# L3D_Main_Board_v2.net
KiCad netlist of a schematic drawn in EAGLE
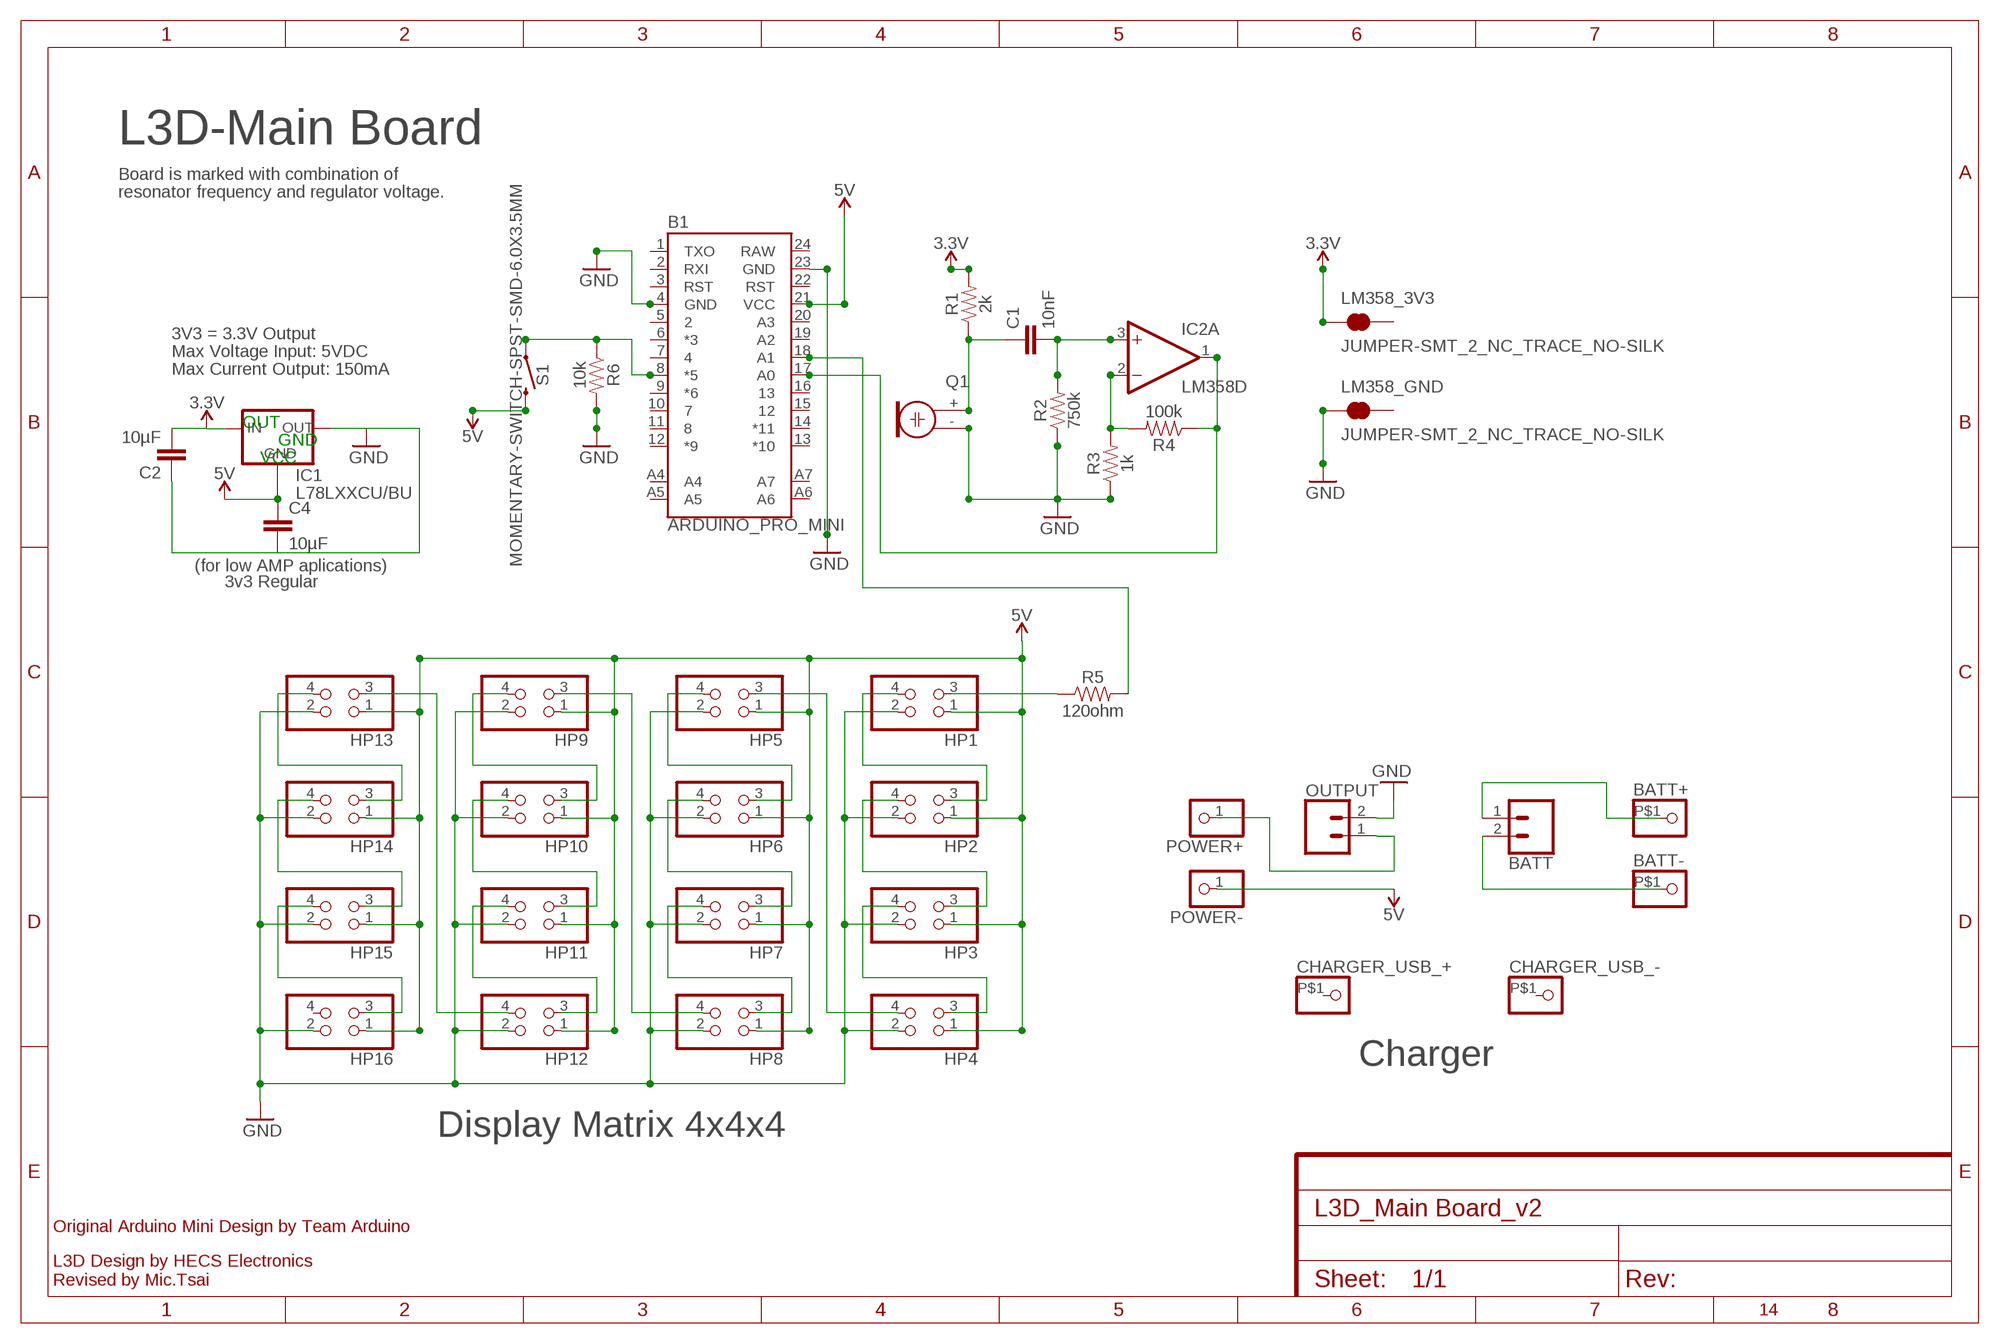
[diagram p0: schematic, sheet 1]

(export (version "E")
  (design (tool "Eeschema 10.0.6"))
  (components
    (comp (ref "B1")
      (value "ARDUINO_PRO_MINI")
      (footprint "eagle-import:ARDUINO_PRO_MINI")
      (libsource (lib "eagle-import") (part "ARDUINO_PRO_MINI"))
    )
    (comp (ref "BATT")
      (value "CONN_02")
      (footprint "eagle-import:1X02")
      (libsource (lib "eagle-import") (part "CONN_02"))
    )
    (comp (ref "BATT+")
      (value "PINHD-1X1-BIGPOGO")
      (footprint "eagle-import:1X1-BIGPOGO")
      (libsource (lib "eagle-import") (part "PINHD-1X1-BIGPOGO"))
    )
    (comp (ref "BATT-")
      (value "PINHD-1X1-BIGPOGO")
      (footprint "eagle-import:1X1-BIGPOGO")
      (libsource (lib "eagle-import") (part "PINHD-1X1-BIGPOGO"))
    )
    (comp (ref "C1")
      (value "10nF")
      (footprint "eagle-import:0805")
      (libsource (lib "eagle-import") (part "0.33UF/330NF-0805-50V-10%"))
    )
    (comp (ref "C2")
      (value "10µF")
      (footprint "eagle-import:0805")
      (libsource (lib "eagle-import") (part "0.33UF/330NF-0805-50V-10%"))
    )
    (comp (ref "C4")
      (value "10µF")
      (footprint "eagle-import:0805")
      (libsource (lib "eagle-import") (part "0.33UF/330NF-0805-50V-10%"))
    )
    (comp (ref "CHARGER_USB_+")
      (value "PINHD-1X1-BIGPOGO")
      (footprint "eagle-import:1X1-BIGPOGO")
      (libsource (lib "eagle-import") (part "PINHD-1X1-BIGPOGO"))
    )
    (comp (ref "CHARGER_USB_-")
      (value "PINHD-1X1-BIGPOGO")
      (footprint "eagle-import:1X1-BIGPOGO")
      (libsource (lib "eagle-import") (part "PINHD-1X1-BIGPOGO"))
    )
    (comp (ref "HP1")
      (value "PINHD-2X2_2.00")
      (footprint "eagle-import:2X02M")
      (libsource (lib "eagle-import") (part "PINHD-2X2_2.00"))
    )
    (comp (ref "HP2")
      (value "PINHD-2X2_2.00")
      (footprint "eagle-import:2X02M")
      (libsource (lib "eagle-import") (part "PINHD-2X2_2.00"))
    )
    (comp (ref "HP3")
      (value "PINHD-2X2_2.00")
      (footprint "eagle-import:2X02M")
      (libsource (lib "eagle-import") (part "PINHD-2X2_2.00"))
    )
    (comp (ref "HP4")
      (value "PINHD-2X2_2.00")
      (footprint "eagle-import:2X02M")
      (libsource (lib "eagle-import") (part "PINHD-2X2_2.00"))
    )
    (comp (ref "HP5")
      (value "PINHD-2X2_2.00")
      (footprint "eagle-import:2X02M")
      (libsource (lib "eagle-import") (part "PINHD-2X2_2.00"))
    )
    (comp (ref "HP6")
      (value "PINHD-2X2_2.00")
      (footprint "eagle-import:2X02M")
      (libsource (lib "eagle-import") (part "PINHD-2X2_2.00"))
    )
    (comp (ref "HP7")
      (value "PINHD-2X2_2.00")
      (footprint "eagle-import:2X02M")
      (libsource (lib "eagle-import") (part "PINHD-2X2_2.00"))
    )
    (comp (ref "HP8")
      (value "PINHD-2X2_2.00")
      (footprint "eagle-import:2X02M")
      (libsource (lib "eagle-import") (part "PINHD-2X2_2.00"))
    )
    (comp (ref "HP9")
      (value "PINHD-2X2_2.00")
      (footprint "eagle-import:2X02M")
      (libsource (lib "eagle-import") (part "PINHD-2X2_2.00"))
    )
    (comp (ref "HP10")
      (value "PINHD-2X2_2.00")
      (footprint "eagle-import:2X02M")
      (libsource (lib "eagle-import") (part "PINHD-2X2_2.00"))
    )
    (comp (ref "HP11")
      (value "PINHD-2X2_2.00")
      (footprint "eagle-import:2X02M")
      (libsource (lib "eagle-import") (part "PINHD-2X2_2.00"))
    )
    (comp (ref "HP12")
      (value "PINHD-2X2_2.00")
      (footprint "eagle-import:2X02M")
      (libsource (lib "eagle-import") (part "PINHD-2X2_2.00"))
    )
    (comp (ref "HP13")
      (value "PINHD-2X2_2.00")
      (footprint "eagle-import:2X02M")
      (libsource (lib "eagle-import") (part "PINHD-2X2_2.00"))
    )
    (comp (ref "HP14")
      (value "PINHD-2X2_2.00")
      (footprint "eagle-import:2X02M")
      (libsource (lib "eagle-import") (part "PINHD-2X2_2.00"))
    )
    (comp (ref "HP15")
      (value "PINHD-2X2_2.00")
      (footprint "eagle-import:2X02M")
      (libsource (lib "eagle-import") (part "PINHD-2X2_2.00"))
    )
    (comp (ref "HP16")
      (value "PINHD-2X2_2.00")
      (footprint "eagle-import:2X02M")
      (libsource (lib "eagle-import") (part "PINHD-2X2_2.00"))
    )
    (comp (ref "IC1")
      (value "L78LXXCU/BU")
      (footprint "eagle-import:SOT89")
      (libsource (lib "eagle-import") (part "L78LXXCU/BU"))
    )
    (comp (ref "IC2")
      (value "LM358D")
      (footprint "eagle-import:SO08")
      (libsource (lib "eagle-import") (part "LM358D"))
    )
    (comp (ref "LM358_3V3")
      (value "JUMPER-SMT_2_NC_TRACE_NO-SILK")
      (footprint "eagle-import:SMT-JUMPER_2_NC_TRACE_NO-SILK")
      (libsource (lib "eagle-import") (part "JUMPER-SMT_2_NC_TRACE_NO-SILK"))
    )
    (comp (ref "LM358_GND")
      (value "JUMPER-SMT_2_NC_TRACE_NO-SILK")
      (footprint "eagle-import:SMT-JUMPER_2_NC_TRACE_NO-SILK")
      (libsource (lib "eagle-import") (part "JUMPER-SMT_2_NC_TRACE_NO-SILK"))
    )
    (comp (ref "OUTPUT")
      (value "CONN_02")
      (footprint "eagle-import:1X02")
      (libsource (lib "eagle-import") (part "CONN_02"))
    )
    (comp (ref "POWER+")
      (value "PINHD-1X1")
      (footprint "eagle-import:1X01")
      (libsource (lib "eagle-import") (part "PINHD-1X1"))
    )
    (comp (ref "POWER-")
      (value "PINHD-1X1")
      (footprint "eagle-import:1X01")
      (libsource (lib "eagle-import") (part "PINHD-1X1"))
    )
    (comp (ref "Q1")
      (value "ELECTRET")
      (footprint "eagle-import:9.7ELECTRET")
      (libsource (lib "eagle-import") (part "ELECTRET"))
    )
    (comp (ref "R1")
      (value "2k")
      (footprint "eagle-import:0603")
      (libsource (lib "eagle-import") (part "820KOHM-0603-1/10W-1%"))
    )
    (comp (ref "R2")
      (value "750k")
      (footprint "eagle-import:0603")
      (libsource (lib "eagle-import") (part "820KOHM-0603-1/10W-1%"))
    )
    (comp (ref "R3")
      (value "1k")
      (footprint "eagle-import:0603")
      (libsource (lib "eagle-import") (part "820KOHM-0603-1/10W-1%"))
    )
    (comp (ref "R4")
      (value "100k")
      (footprint "eagle-import:0603")
      (libsource (lib "eagle-import") (part "820KOHM-0603-1/10W-1%"))
    )
    (comp (ref "R5")
      (value "120ohm")
      (footprint "eagle-import:1210")
      (libsource (lib "eagle-import") (part "0.1OHM-1210-1/2W-1%"))
    )
    (comp (ref "R6")
      (value "10k")
      (footprint "eagle-import:0603")
      (libsource (lib "eagle-import") (part "820KOHM-0603-1/10W-1%"))
    )
    (comp (ref "S1")
      (value "MOMENTARY-SWITCH-SPST-SMD-6.0X3.5MM")
      (footprint "eagle-import:TACTILE_SWITCH_SMD_6.0X3.5MM")
      (libsource (lib "eagle-import") (part "MOMENTARY-SWITCH-SPST-SMD-6.0X3.5MM"))
    )
  )
  (nets
    (net (code "1") (name "/RAW") (class "Default")
      (node (ref "B1") (pin "24") (pinfunction "RAW_24") (pintype "power_in"))
    )
    (net (code "2") (name "3.3V") (class "Default")
      (node (ref "C2") (pin "2") (pinfunction "2_2") (pintype "passive"))
      (node (ref "IC1") (pin "3") (pinfunction "IN_3") (pintype "input"))
      (node (ref "LM358_3V3") (pin "1") (pinfunction "1_1") (pintype "passive"))
      (node (ref "R1") (pin "2") (pinfunction "2_2") (pintype "passive"))
    )
    (net (code "3") (name "5V") (class "Default")
      (node (ref "B1") (pin "21") (pinfunction "VCC_21") (pintype "power_in"))
      (node (ref "C4") (pin "1") (pinfunction "1_1") (pintype "passive"))
      (node (ref "HP1") (pin "1") (pinfunction "1_1") (pintype "passive"))
      (node (ref "HP10") (pin "1") (pinfunction "1_1") (pintype "passive"))
      (node (ref "HP11") (pin "1") (pinfunction "1_1") (pintype "passive"))
      (node (ref "HP12") (pin "1") (pinfunction "1_1") (pintype "passive"))
      (node (ref "HP13") (pin "1") (pinfunction "1_1") (pintype "passive"))
      (node (ref "HP14") (pin "1") (pinfunction "1_1") (pintype "passive"))
      (node (ref "HP15") (pin "1") (pinfunction "1_1") (pintype "passive"))
      (node (ref "HP16") (pin "1") (pinfunction "1_1") (pintype "passive"))
      (node (ref "HP2") (pin "1") (pinfunction "1_1") (pintype "passive"))
      (node (ref "HP3") (pin "1") (pinfunction "1_1") (pintype "passive"))
      (node (ref "HP4") (pin "1") (pinfunction "1_1") (pintype "passive"))
      (node (ref "HP5") (pin "1") (pinfunction "1_1") (pintype "passive"))
      (node (ref "HP6") (pin "1") (pinfunction "1_1") (pintype "passive"))
      (node (ref "HP7") (pin "1") (pinfunction "1_1") (pintype "passive"))
      (node (ref "HP8") (pin "1") (pinfunction "1_1") (pintype "passive"))
      (node (ref "HP9") (pin "1") (pinfunction "1_1") (pintype "passive"))
      (node (ref "IC1") (pin "4") (pinfunction "GND1_4") (pintype "input"))
      (node (ref "POWER-") (pin "1") (pinfunction "1_1") (pintype "passive"))
      (node (ref "S1") (pin "2") (pinfunction "2_2") (pintype "passive"))
    )
    (net (code "4") (name "GND") (class "Default")
      (node (ref "B1") (pin "23") (pinfunction "GND_23") (pintype "power_in"))
      (node (ref "B1") (pin "4") (pinfunction "GND_4") (pintype "power_in"))
      (node (ref "C2") (pin "1") (pinfunction "1_1") (pintype "passive"))
      (node (ref "C4") (pin "2") (pinfunction "2_2") (pintype "passive"))
      (node (ref "HP1") (pin "2") (pinfunction "2_2") (pintype "passive"))
      (node (ref "HP10") (pin "2") (pinfunction "2_2") (pintype "passive"))
      (node (ref "HP11") (pin "2") (pinfunction "2_2") (pintype "passive"))
      (node (ref "HP12") (pin "2") (pinfunction "2_2") (pintype "passive"))
      (node (ref "HP13") (pin "2") (pinfunction "2_2") (pintype "passive"))
      (node (ref "HP14") (pin "2") (pinfunction "2_2") (pintype "passive"))
      (node (ref "HP15") (pin "2") (pinfunction "2_2") (pintype "passive"))
      (node (ref "HP16") (pin "2") (pinfunction "2_2") (pintype "passive"))
      (node (ref "HP2") (pin "2") (pinfunction "2_2") (pintype "passive"))
      (node (ref "HP3") (pin "2") (pinfunction "2_2") (pintype "passive"))
      (node (ref "HP4") (pin "2") (pinfunction "2_2") (pintype "passive"))
      (node (ref "HP5") (pin "2") (pinfunction "2_2") (pintype "passive"))
      (node (ref "HP6") (pin "2") (pinfunction "2_2") (pintype "passive"))
      (node (ref "HP7") (pin "2") (pinfunction "2_2") (pintype "passive"))
      (node (ref "HP8") (pin "2") (pinfunction "2_2") (pintype "passive"))
      (node (ref "HP9") (pin "2") (pinfunction "2_2") (pintype "passive"))
      (node (ref "IC1") (pin "1") (pinfunction "OUT_1") (pintype "passive"))
      (node (ref "LM358_GND") (pin "1") (pinfunction "1_1") (pintype "passive"))
      (node (ref "OUTPUT") (pin "2") (pinfunction "2_2") (pintype "passive"))
      (node (ref "Q1") (pin "-") (pinfunction "1_-") (pintype "passive"))
      (node (ref "R2") (pin "1") (pinfunction "1_1") (pintype "passive"))
      (node (ref "R3") (pin "1") (pinfunction "1_1") (pintype "passive"))
      (node (ref "R6") (pin "2") (pinfunction "2_2") (pintype "passive"))
    )
    (net (code "5") (name "Net-(B1-*5)") (class "Default")
      (node (ref "B1") (pin "8") (pinfunction "*5_8") (pintype "bidirectional"))
      (node (ref "R6") (pin "1") (pinfunction "1_1") (pintype "passive"))
      (node (ref "S1") (pin "1") (pinfunction "1_1") (pintype "passive"))
    )
    (net (code "6") (name "Net-(B1-A0)") (class "Default")
      (node (ref "B1") (pin "17") (pinfunction "A0_17") (pintype "bidirectional"))
      (node (ref "IC2") (pin "1") (pinfunction "OUT_1") (pintype "output"))
      (node (ref "R4") (pin "1") (pinfunction "1_1") (pintype "passive"))
    )
    (net (code "7") (name "Net-(B1-A1)") (class "Default")
      (node (ref "B1") (pin "18") (pinfunction "A1_18") (pintype "bidirectional"))
      (node (ref "R5") (pin "2") (pinfunction "2_2") (pintype "passive"))
    )
    (net (code "8") (name "Net-(BATT+-1)") (class "Default")
      (node (ref "BATT") (pin "1") (pinfunction "1_1") (pintype "passive"))
      (node (ref "BATT+") (pin "P$1") (pinfunction "1_P$1") (pintype "passive"))
    )
    (net (code "9") (name "Net-(BATT--1)") (class "Default")
      (node (ref "BATT") (pin "2") (pinfunction "2_2") (pintype "passive"))
      (node (ref "BATT-") (pin "P$1") (pinfunction "1_P$1") (pintype "passive"))
    )
    (net (code "10") (name "Net-(HP1-Pad3)") (class "Default")
      (node (ref "HP1") (pin "3") (pinfunction "3_3") (pintype "passive"))
      (node (ref "R5") (pin "1") (pinfunction "1_1") (pintype "passive"))
    )
    (net (code "11") (name "Net-(HP1-Pad4)") (class "Default")
      (node (ref "HP1") (pin "4") (pinfunction "4_4") (pintype "passive"))
      (node (ref "HP2") (pin "3") (pinfunction "3_3") (pintype "passive"))
    )
    (net (code "12") (name "Net-(HP2-Pad4)") (class "Default")
      (node (ref "HP2") (pin "4") (pinfunction "4_4") (pintype "passive"))
      (node (ref "HP3") (pin "3") (pinfunction "3_3") (pintype "passive"))
    )
    (net (code "13") (name "Net-(HP3-Pad4)") (class "Default")
      (node (ref "HP3") (pin "4") (pinfunction "4_4") (pintype "passive"))
      (node (ref "HP4") (pin "3") (pinfunction "3_3") (pintype "passive"))
    )
    (net (code "14") (name "Net-(HP4-Pad4)") (class "Default")
      (node (ref "HP4") (pin "4") (pinfunction "4_4") (pintype "passive"))
      (node (ref "HP5") (pin "3") (pinfunction "3_3") (pintype "passive"))
    )
    (net (code "15") (name "Net-(HP5-Pad4)") (class "Default")
      (node (ref "HP5") (pin "4") (pinfunction "4_4") (pintype "passive"))
      (node (ref "HP6") (pin "3") (pinfunction "3_3") (pintype "passive"))
    )
    (net (code "16") (name "Net-(HP6-Pad4)") (class "Default")
      (node (ref "HP6") (pin "4") (pinfunction "4_4") (pintype "passive"))
      (node (ref "HP7") (pin "3") (pinfunction "3_3") (pintype "passive"))
    )
    (net (code "17") (name "Net-(HP7-Pad4)") (class "Default")
      (node (ref "HP7") (pin "4") (pinfunction "4_4") (pintype "passive"))
      (node (ref "HP8") (pin "3") (pinfunction "3_3") (pintype "passive"))
    )
    (net (code "18") (name "Net-(HP8-Pad4)") (class "Default")
      (node (ref "HP8") (pin "4") (pinfunction "4_4") (pintype "passive"))
      (node (ref "HP9") (pin "3") (pinfunction "3_3") (pintype "passive"))
    )
    (net (code "19") (name "Net-(HP10-Pad3)") (class "Default")
      (node (ref "HP10") (pin "3") (pinfunction "3_3") (pintype "passive"))
      (node (ref "HP9") (pin "4") (pinfunction "4_4") (pintype "passive"))
    )
    (net (code "20") (name "Net-(HP10-Pad4)") (class "Default")
      (node (ref "HP10") (pin "4") (pinfunction "4_4") (pintype "passive"))
      (node (ref "HP11") (pin "3") (pinfunction "3_3") (pintype "passive"))
    )
    (net (code "21") (name "Net-(HP11-Pad4)") (class "Default")
      (node (ref "HP11") (pin "4") (pinfunction "4_4") (pintype "passive"))
      (node (ref "HP12") (pin "3") (pinfunction "3_3") (pintype "passive"))
    )
    (net (code "22") (name "Net-(HP12-Pad4)") (class "Default")
      (node (ref "HP12") (pin "4") (pinfunction "4_4") (pintype "passive"))
      (node (ref "HP13") (pin "3") (pinfunction "3_3") (pintype "passive"))
    )
    (net (code "23") (name "Net-(HP13-Pad4)") (class "Default")
      (node (ref "HP13") (pin "4") (pinfunction "4_4") (pintype "passive"))
      (node (ref "HP14") (pin "3") (pinfunction "3_3") (pintype "passive"))
    )
    (net (code "24") (name "Net-(HP14-Pad4)") (class "Default")
      (node (ref "HP14") (pin "4") (pinfunction "4_4") (pintype "passive"))
      (node (ref "HP15") (pin "3") (pinfunction "3_3") (pintype "passive"))
    )
    (net (code "25") (name "Net-(HP15-Pad4)") (class "Default")
      (node (ref "HP15") (pin "4") (pinfunction "4_4") (pintype "passive"))
      (node (ref "HP16") (pin "3") (pinfunction "3_3") (pintype "passive"))
    )
    (net (code "26") (name "Net-(IC2A-+IN)") (class "Default")
      (node (ref "C1") (pin "2") (pinfunction "2_2") (pintype "passive"))
      (node (ref "IC2") (pin "3") (pinfunction "+IN_3") (pintype "input"))
      (node (ref "R2") (pin "2") (pinfunction "2_2") (pintype "passive"))
    )
    (net (code "27") (name "Net-(IC2A--IN)") (class "Default")
      (node (ref "IC2") (pin "2") (pinfunction "-IN_2") (pintype "input"))
      (node (ref "R3") (pin "2") (pinfunction "2_2") (pintype "passive"))
      (node (ref "R4") (pin "2") (pinfunction "2_2") (pintype "passive"))
    )
    (net (code "28") (name "Net-(OUTPUT-Pad1)") (class "Default")
      (node (ref "OUTPUT") (pin "1") (pinfunction "1_1") (pintype "passive"))
      (node (ref "POWER+") (pin "1") (pinfunction "1_1") (pintype "passive"))
    )
    (net (code "29") (name "Net-(Q1-2)") (class "Default")
      (node (ref "C1") (pin "1") (pinfunction "1_1") (pintype "passive"))
      (node (ref "Q1") (pin "+") (pinfunction "2_+") (pintype "passive"))
      (node (ref "R1") (pin "1") (pinfunction "1_1") (pintype "passive"))
    )
    (net (code "30") (name "unconnected-(B1-*3-Pad6)") (class "Default")
      (node (ref "B1") (pin "6") (pinfunction "*3_6") (pintype "bidirectional"))
    )
    (net (code "31") (name "unconnected-(B1-*6-Pad9)") (class "Default")
      (node (ref "B1") (pin "9") (pinfunction "*6_9") (pintype "bidirectional"))
    )
    (net (code "32") (name "unconnected-(B1-*9-Pad12)") (class "Default")
      (node (ref "B1") (pin "12") (pinfunction "*9_12") (pintype "bidirectional"))
    )
    (net (code "33") (name "unconnected-(B1-*10-Pad13)") (class "Default")
      (node (ref "B1") (pin "13") (pinfunction "*10_13") (pintype "bidirectional"))
    )
    (net (code "34") (name "unconnected-(B1-*11-Pad14)") (class "Default")
      (node (ref "B1") (pin "14") (pinfunction "*11_14") (pintype "bidirectional"))
    )
    (net (code "35") (name "unconnected-(B1-2-Pad5)") (class "Default")
      (node (ref "B1") (pin "5") (pinfunction "2_5") (pintype "bidirectional"))
    )
    (net (code "36") (name "unconnected-(B1-4-Pad7)") (class "Default")
      (node (ref "B1") (pin "7") (pinfunction "4_7") (pintype "bidirectional"))
    )
    (net (code "37") (name "unconnected-(B1-7-Pad10)") (class "Default")
      (node (ref "B1") (pin "10") (pinfunction "7_10") (pintype "bidirectional"))
    )
    (net (code "38") (name "unconnected-(B1-8-Pad11)") (class "Default")
      (node (ref "B1") (pin "11") (pinfunction "8_11") (pintype "bidirectional"))
    )
    (net (code "39") (name "unconnected-(B1-12-Pad15)") (class "Default")
      (node (ref "B1") (pin "15") (pinfunction "12_15") (pintype "bidirectional"))
    )
    (net (code "40") (name "unconnected-(B1-13-Pad16)") (class "Default")
      (node (ref "B1") (pin "16") (pinfunction "13_16") (pintype "bidirectional"))
    )
    (net (code "41") (name "unconnected-(B1-A2-Pad19)") (class "Default")
      (node (ref "B1") (pin "19") (pinfunction "A2_19") (pintype "bidirectional"))
    )
    (net (code "42") (name "unconnected-(B1-A3-Pad20)") (class "Default")
      (node (ref "B1") (pin "20") (pinfunction "A3_20") (pintype "bidirectional"))
    )
    (net (code "43") (name "unconnected-(B1-PadA4)") (class "Default")
      (node (ref "B1") (pin "A4") (pinfunction "A4_A4") (pintype "bidirectional"))
    )
    (net (code "44") (name "unconnected-(B1-PadA5)") (class "Default")
      (node (ref "B1") (pin "A5") (pinfunction "A5_A5") (pintype "bidirectional"))
    )
    (net (code "45") (name "unconnected-(B1-PadA6)") (class "Default")
      (node (ref "B1") (pin "A6") (pinfunction "A6_A6") (pintype "bidirectional"))
    )
    (net (code "46") (name "unconnected-(B1-PadA7)") (class "Default")
      (node (ref "B1") (pin "A7") (pinfunction "A7_A7") (pintype "bidirectional"))
    )
    (net (code "47") (name "unconnected-(B1-RST-Pad3)") (class "Default")
      (node (ref "B1") (pin "3") (pinfunction "RST_3") (pintype "bidirectional"))
    )
    (net (code "48") (name "unconnected-(B1-RST-Pad22)") (class "Default")
      (node (ref "B1") (pin "22") (pinfunction "RST_22") (pintype "bidirectional"))
    )
    (net (code "49") (name "unconnected-(B1-RXI-Pad2)") (class "Default")
      (node (ref "B1") (pin "2") (pinfunction "RXI_2") (pintype "bidirectional"))
    )
    (net (code "50") (name "unconnected-(B1-TXO-Pad1)") (class "Default")
      (node (ref "B1") (pin "1") (pinfunction "TXO_1") (pintype "bidirectional"))
    )
    (net (code "51") (name "unconnected-(CHARGER_USB_+-1-PadP$1)") (class "Default")
      (node (ref "CHARGER_USB_+") (pin "P$1") (pinfunction "1_P$1") (pintype "passive"))
    )
    (net (code "52") (name "unconnected-(CHARGER_USB_--1-PadP$1)") (class "Default")
      (node (ref "CHARGER_USB_-") (pin "P$1") (pinfunction "1_P$1") (pintype "passive"))
    )
    (net (code "53") (name "unconnected-(HP16-Pad4)") (class "Default")
      (node (ref "HP16") (pin "4") (pinfunction "4_4") (pintype "passive"))
    )
    (net (code "54") (name "unconnected-(IC1-GND-Pad2)") (class "Default")
      (node (ref "IC1") (pin "2") (pinfunction "GND_2") (pintype "input"))
    )
    (net (code "55") (name "unconnected-(LM358_3V3-Pad2)") (class "Default")
      (node (ref "LM358_3V3") (pin "2") (pinfunction "2_2") (pintype "passive"))
    )
    (net (code "56") (name "unconnected-(LM358_GND-Pad2)") (class "Default")
      (node (ref "LM358_GND") (pin "2") (pinfunction "2_2") (pintype "passive"))
    )
  )
)
